# BattleBoard.net
KiCad netlist of a schematic drawn in EasyEDA
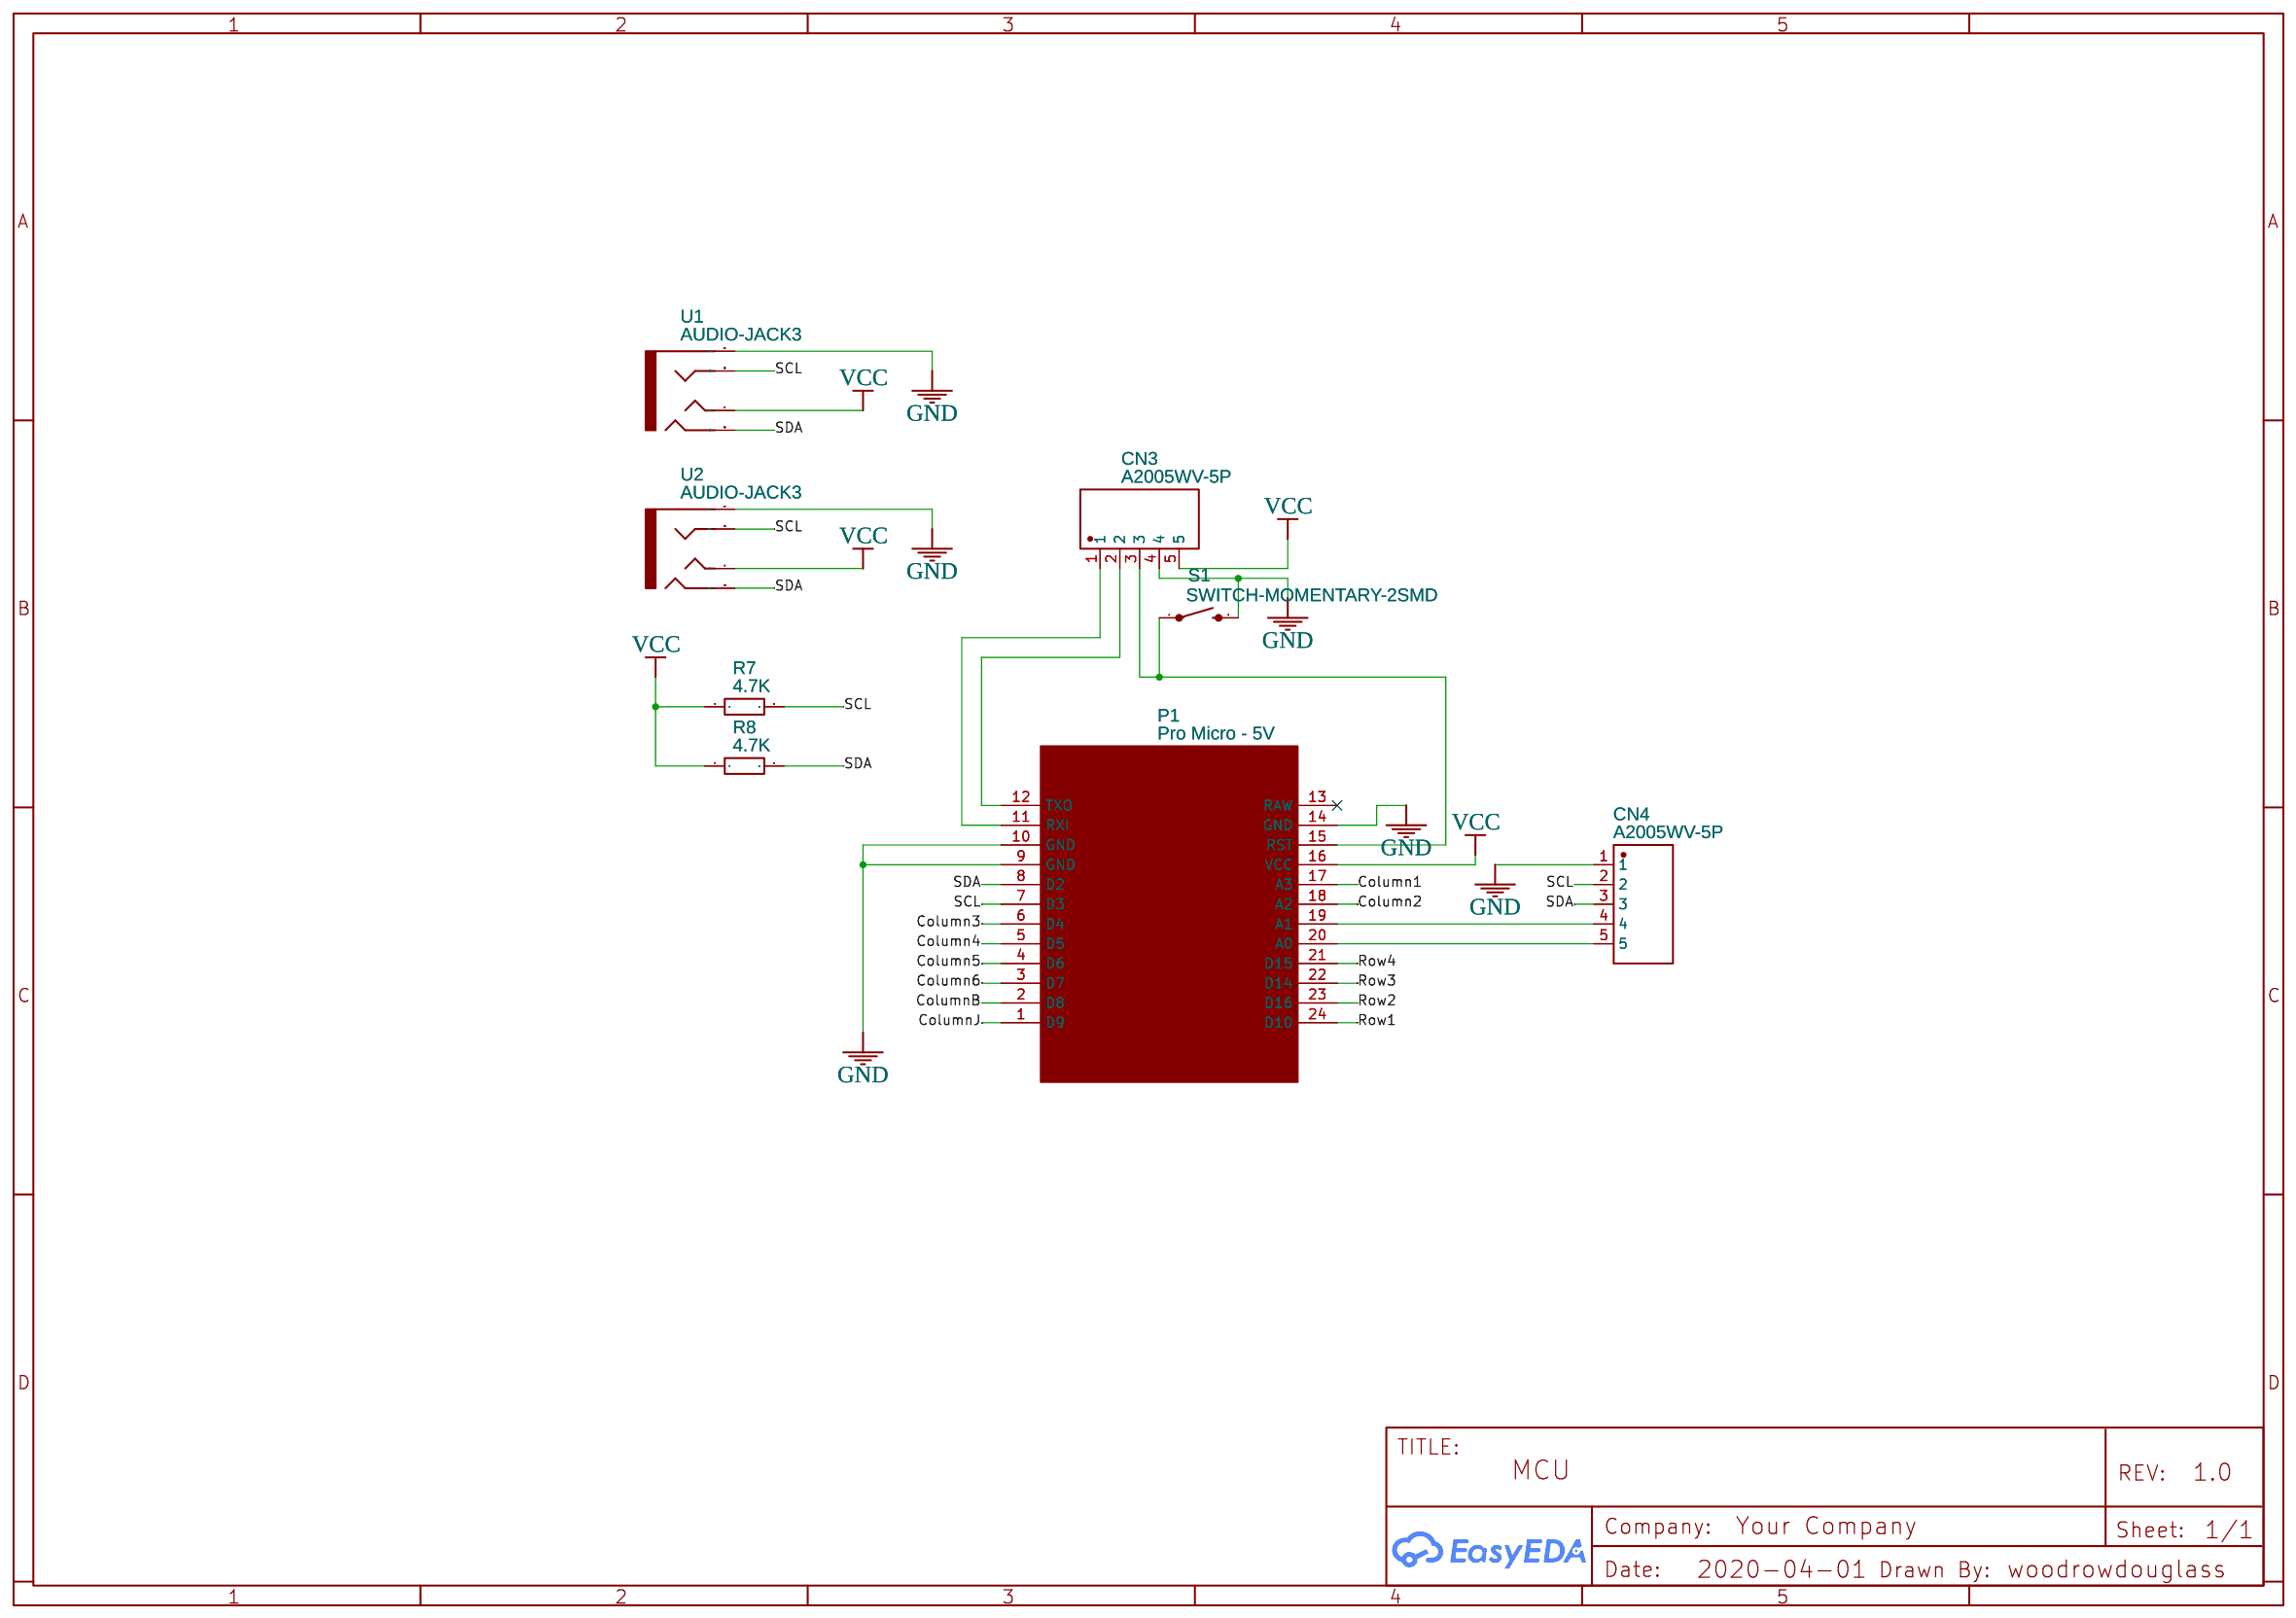
[diagram p0: MCU]
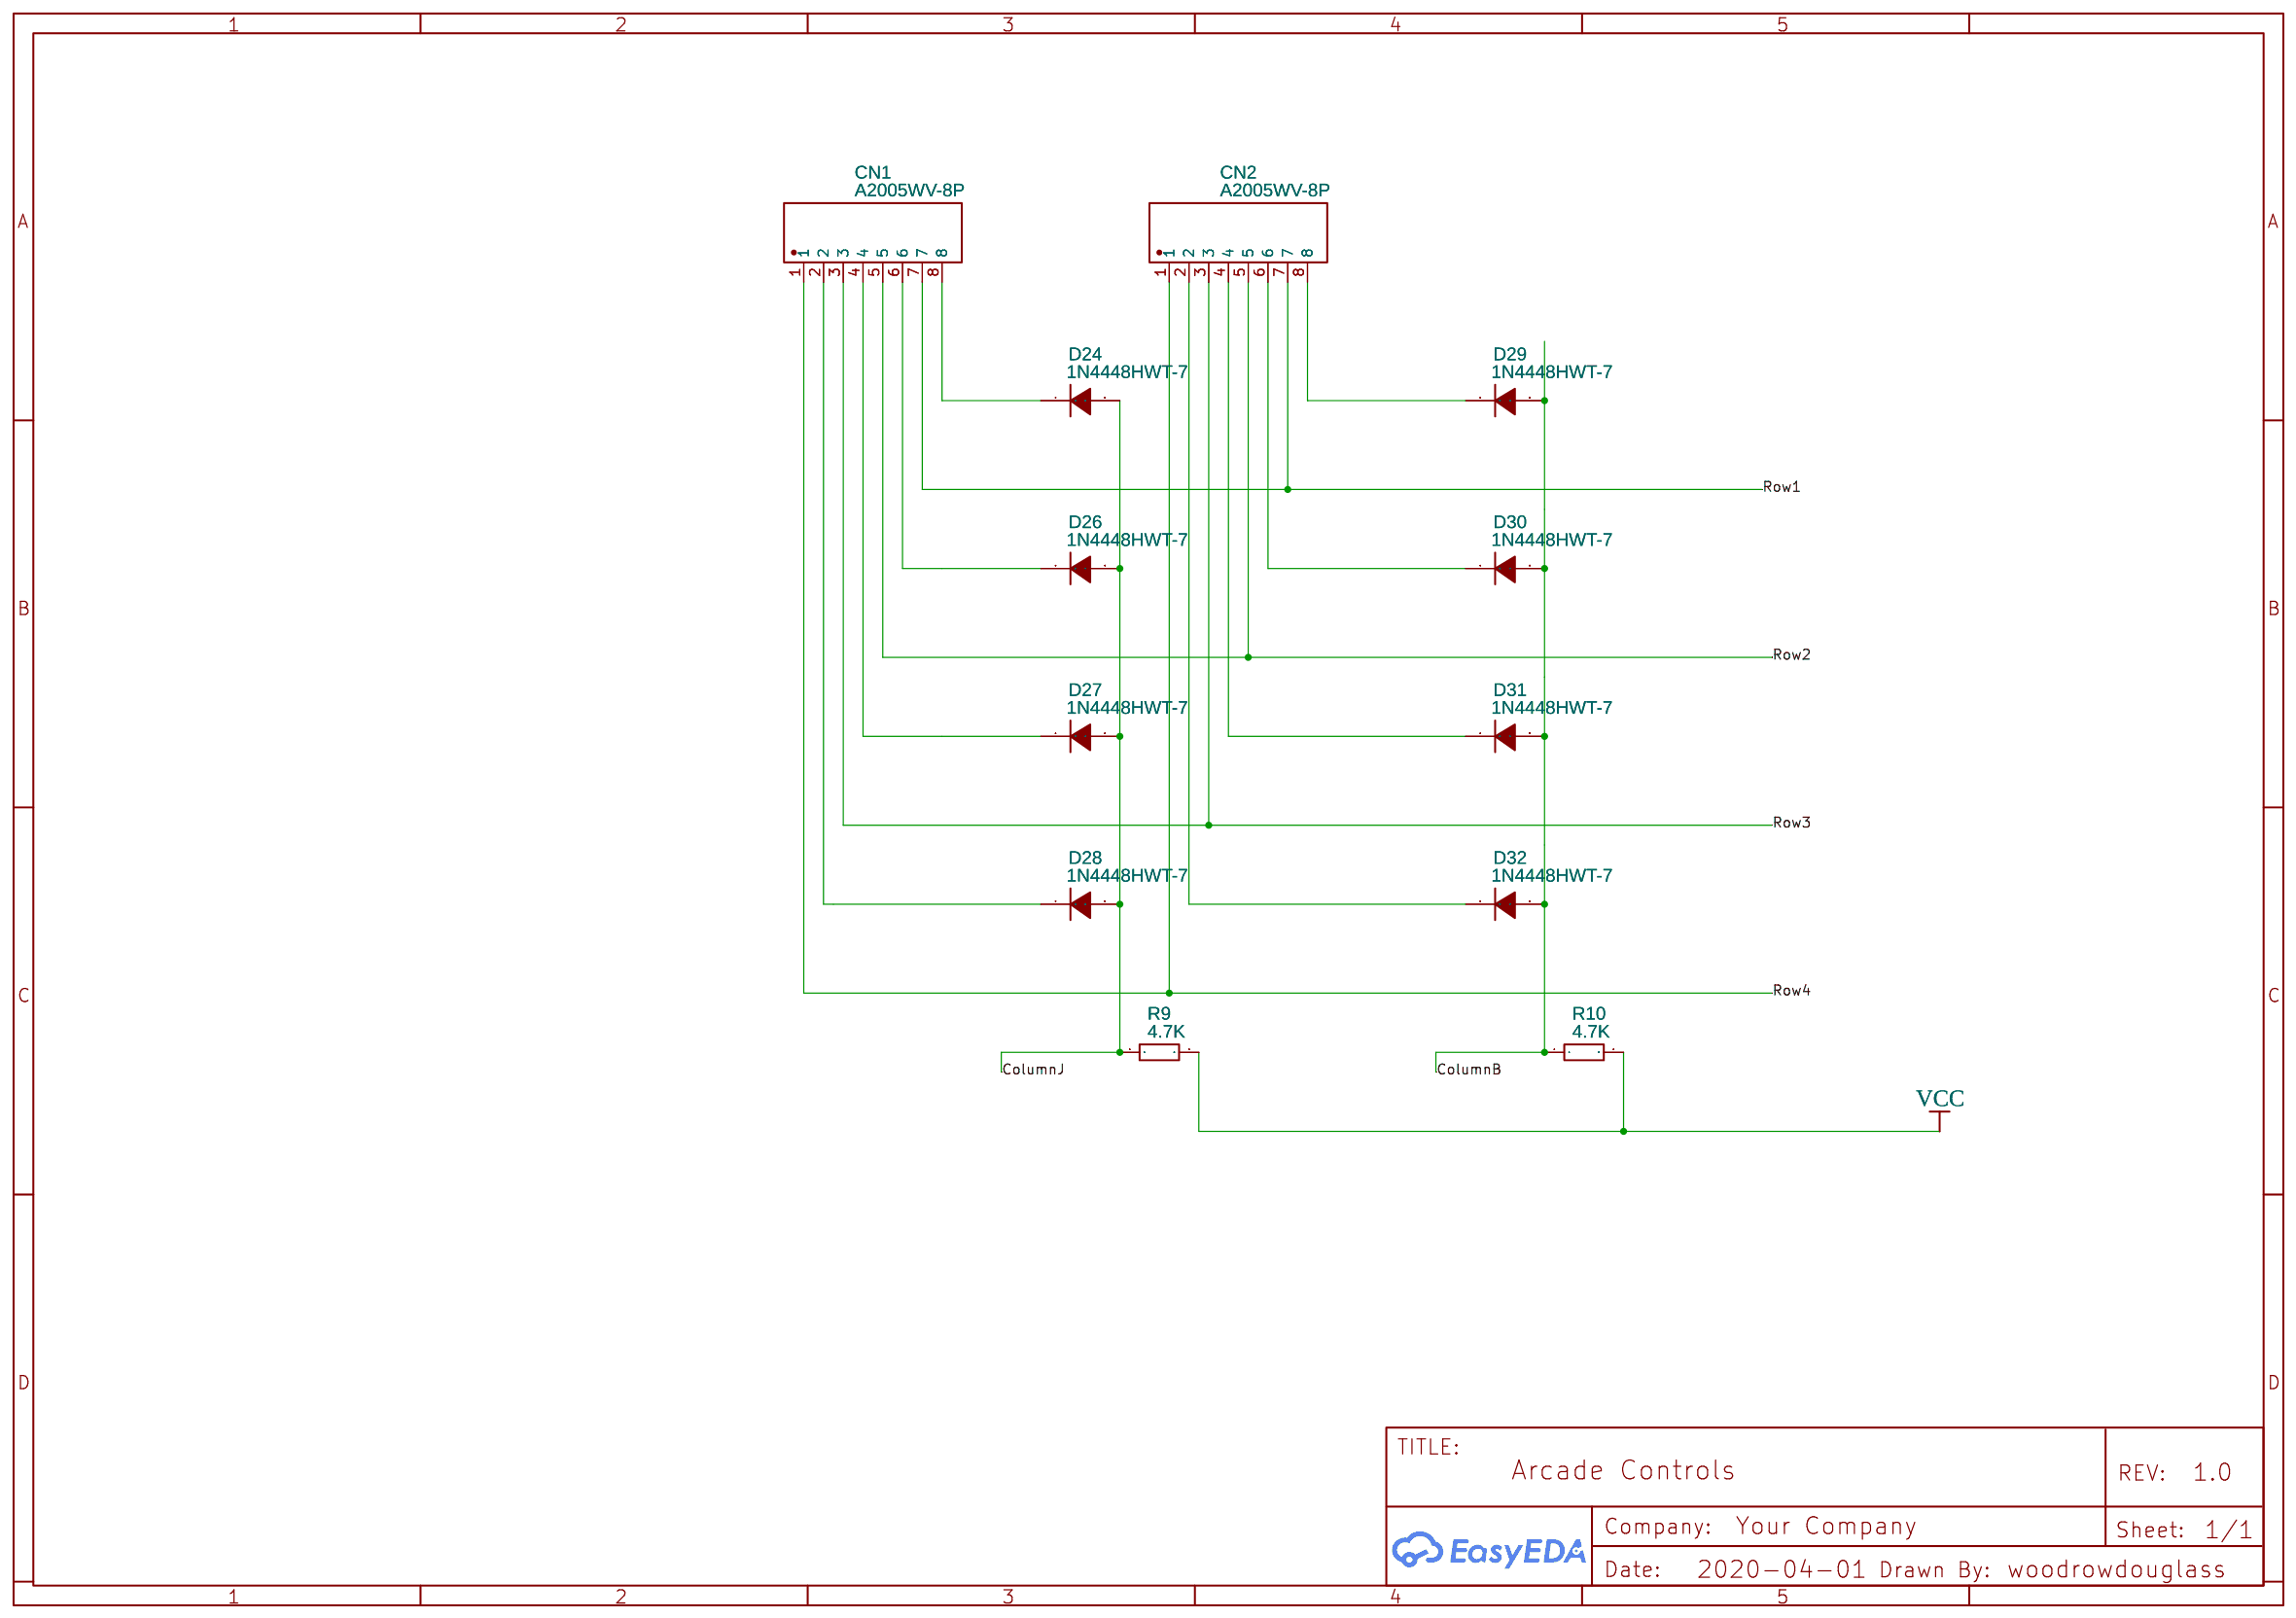
[diagram p1: ArcadeControls]
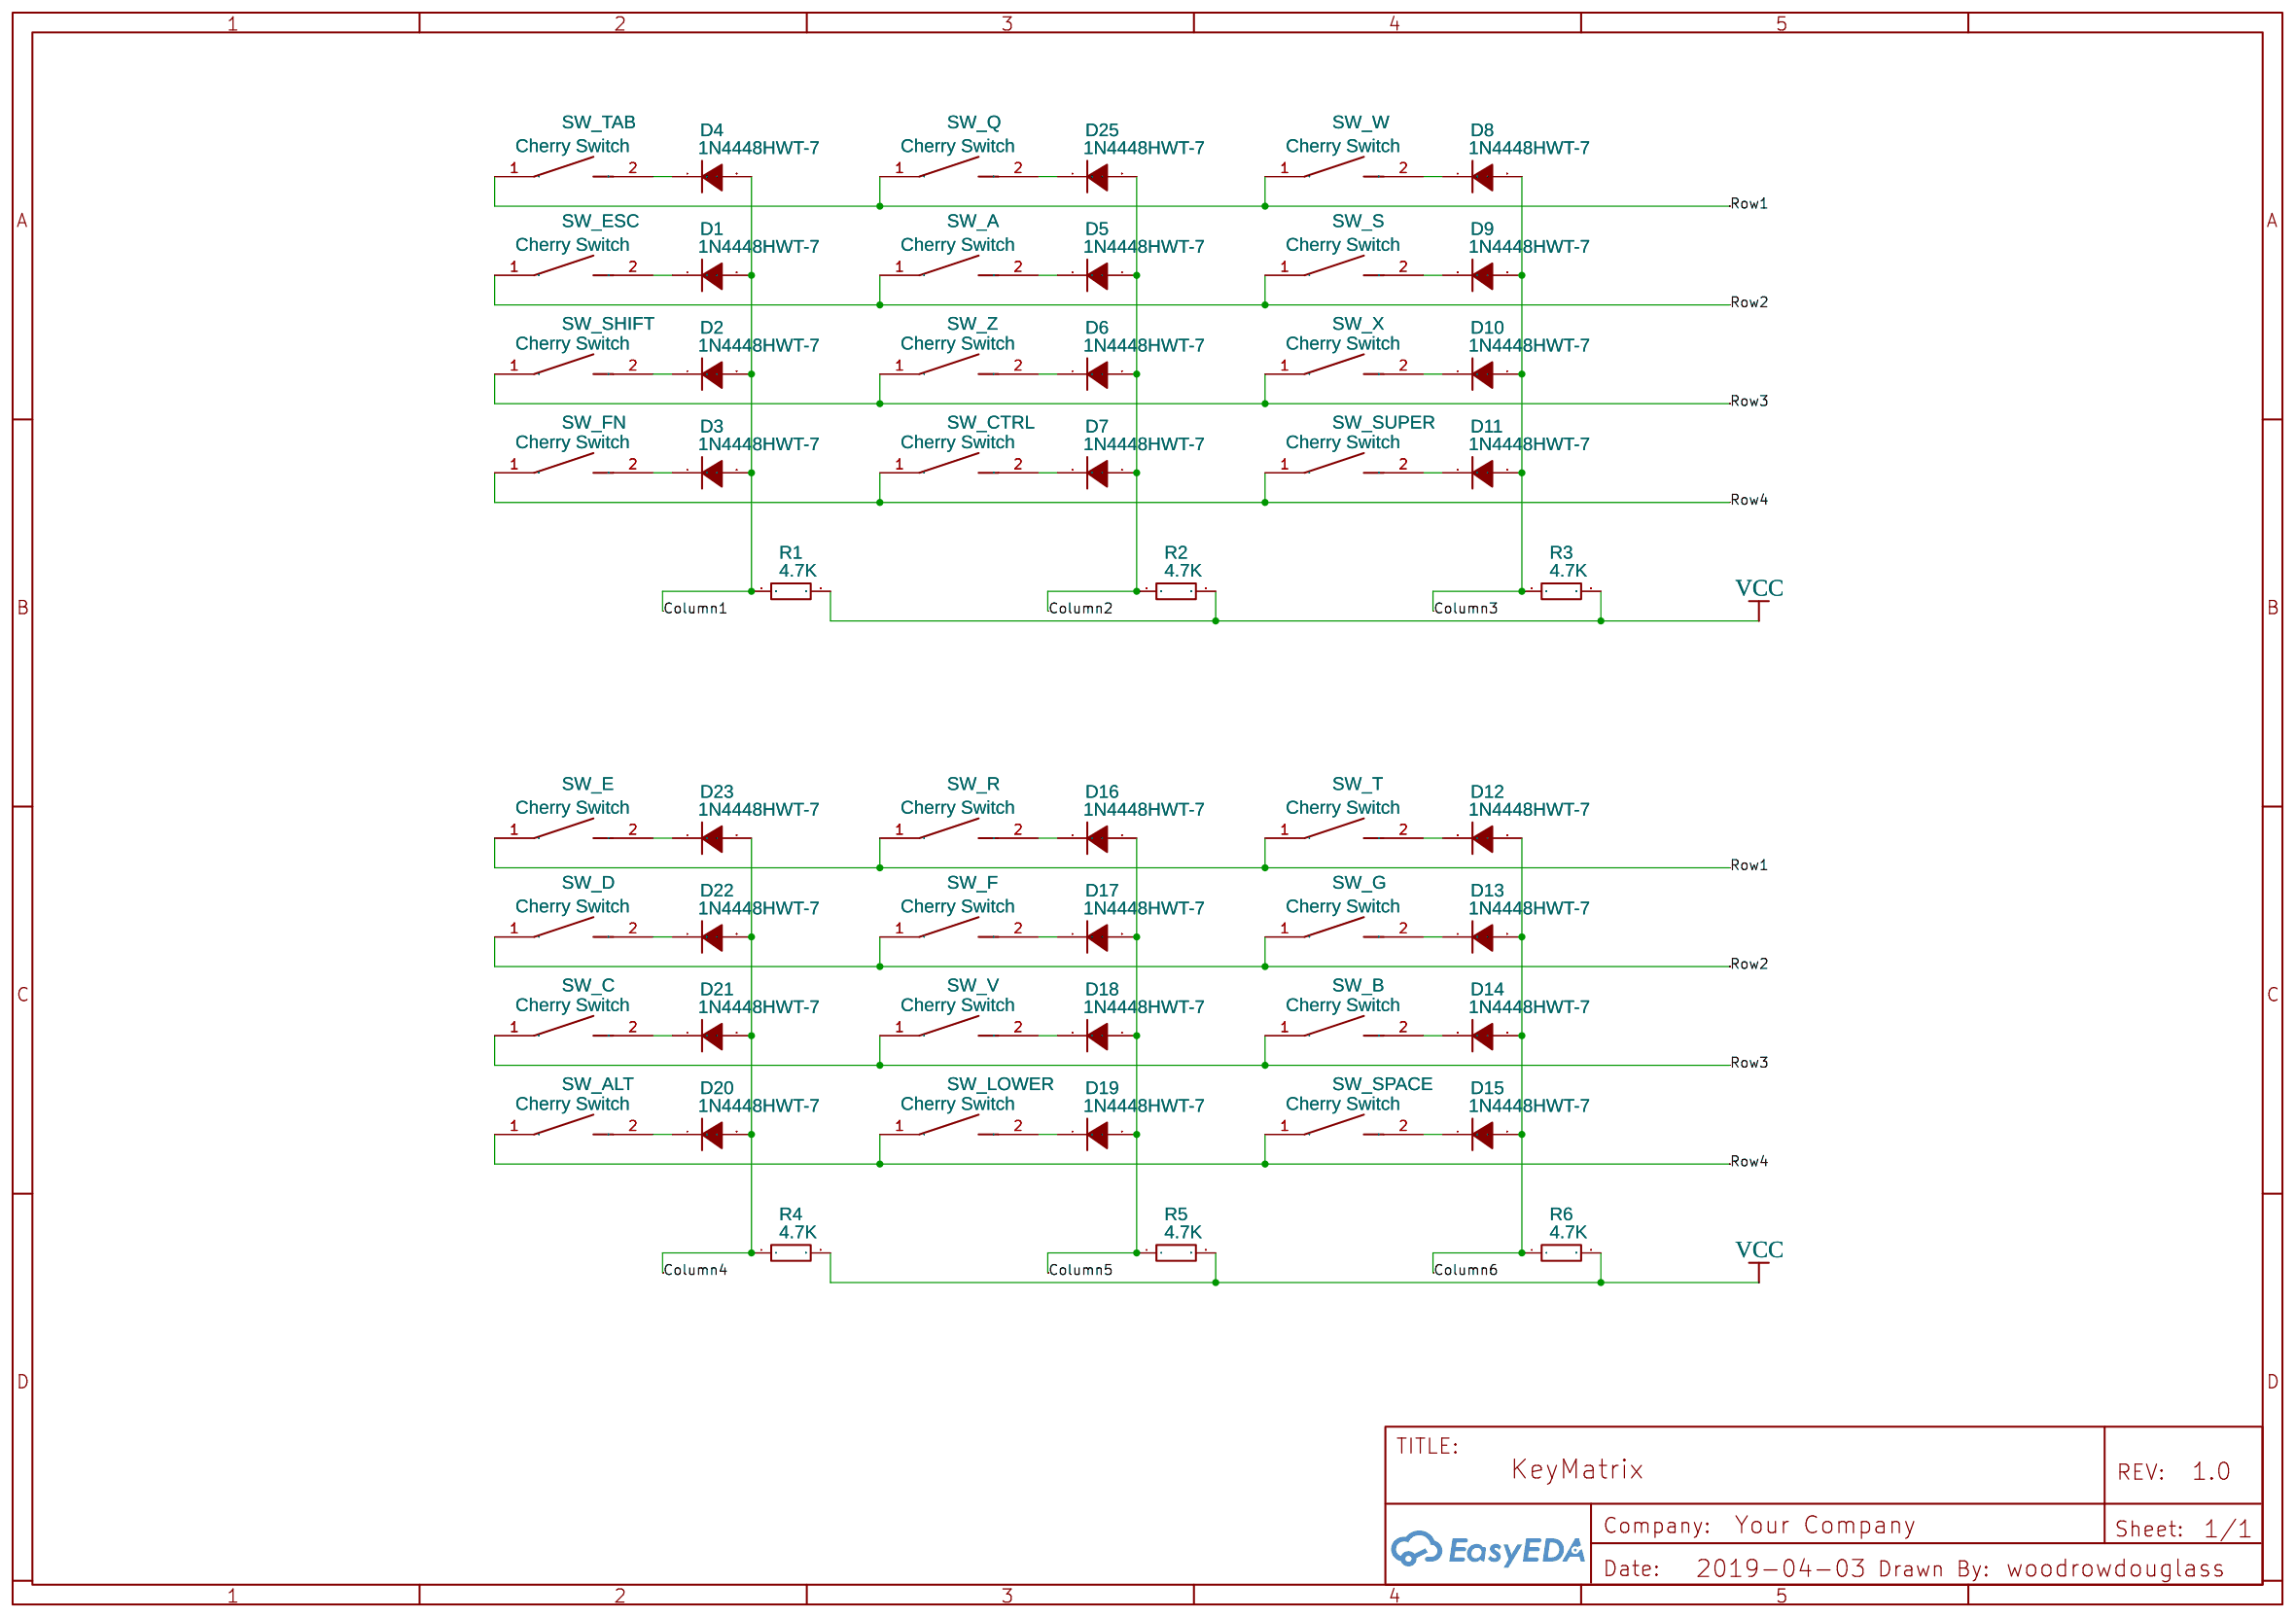
[diagram p2: KeyMatrix]

(export (version "E")
  (design (tool "Eeschema 10.0.6"))
  (components
    (comp (ref "CN3")
      (value "A2005WV-5P")
      (fields (field (name "BOM_Supplier Part") "C225257"))
      (libsource (lib "") (part "A2005WV-5P"))
    )
    (comp (ref "CN4")
      (value "A2005WV-5P")
      (fields (field (name "BOM_Supplier Part") "C225257"))
      (libsource (lib "") (part "A2005WV-5P_1"))
    )
    (comp (ref "P1")
      (value "Pro Micro - 5V")
      (fields (field (name "BOM_Manufacturer Part") "?"))
      (libsource (lib "") (part "Unknown_585_-350"))
    )
    (comp (ref "R7")
      (value "4.7K")
      (fields
        (field (name "BOM_Manufacturer Part") "RMC1/16S-472JTH-M")
        (field (name "BOM_Supplier Part") "C340535")
      )
      (libsource (lib "") (part "RMC1/16S-472JTH-M"))
    )
    (comp (ref "R8")
      (value "4.7K")
      (fields
        (field (name "BOM_Manufacturer Part") "RMC1/16S-472JTH-M")
        (field (name "BOM_Supplier Part") "C340535")
      )
      (libsource (lib "") (part "RMC1/16S-472JTH-M"))
    )
    (comp (ref "S1") (value "SWITCH-MOMENTARY-2SMD") (libsource (lib "") (part "SWITCH-MOMENTARY-2SMD")))
    (comp (ref "U1") (value "AUDIO-JACK3") (libsource (lib "") (part "AUDIO-JACK3")))
    (comp (ref "U2") (value "AUDIO-JACK3") (libsource (lib "") (part "AUDIO-JACK3")))
    (comp (ref "CN1")
      (value "A2005WV-8P")
      (fields (field (name "BOM_Supplier Part") "C225260"))
      (libsource (lib "") (part "A2005WV-8P"))
    )
    (comp (ref "CN2")
      (value "A2005WV-8P")
      (fields (field (name "BOM_Supplier Part") "C225260"))
      (libsource (lib "") (part "A2005WV-8P"))
    )
    (comp (ref "D24")
      (value "1N4448HWT-7")
      (fields (field (name "BOM_Supplier Part") "C139447"))
      (libsource (lib "") (part "1N4448HWT-7"))
    )
    (comp (ref "D26")
      (value "1N4448HWT-7")
      (fields (field (name "BOM_Supplier Part") "C139447"))
      (libsource (lib "") (part "1N4448HWT-7"))
    )
    (comp (ref "D27")
      (value "1N4448HWT-7")
      (fields (field (name "BOM_Supplier Part") "C139447"))
      (libsource (lib "") (part "1N4448HWT-7"))
    )
    (comp (ref "D28")
      (value "1N4448HWT-7")
      (fields (field (name "BOM_Supplier Part") "C139447"))
      (libsource (lib "") (part "1N4448HWT-7"))
    )
    (comp (ref "D29")
      (value "1N4448HWT-7")
      (fields (field (name "BOM_Supplier Part") "C139447"))
      (libsource (lib "") (part "1N4448HWT-7"))
    )
    (comp (ref "D30")
      (value "1N4448HWT-7")
      (fields (field (name "BOM_Supplier Part") "C139447"))
      (libsource (lib "") (part "1N4448HWT-7"))
    )
    (comp (ref "D31")
      (value "1N4448HWT-7")
      (fields (field (name "BOM_Supplier Part") "C139447"))
      (libsource (lib "") (part "1N4448HWT-7"))
    )
    (comp (ref "D32")
      (value "1N4448HWT-7")
      (fields (field (name "BOM_Supplier Part") "C139447"))
      (libsource (lib "") (part "1N4448HWT-7"))
    )
    (comp (ref "R9")
      (value "4.7K")
      (fields
        (field (name "BOM_Manufacturer Part") "RMC1/16S-472JTH-M")
        (field (name "BOM_Supplier Part") "C340535")
      )
      (libsource (lib "") (part "RMC1/16S-472JTH-M"))
    )
    (comp (ref "R10")
      (value "4.7K")
      (fields
        (field (name "BOM_Manufacturer Part") "RMC1/16S-472JTH-M")
        (field (name "BOM_Supplier Part") "C340535")
      )
      (libsource (lib "") (part "RMC1/16S-472JTH-M"))
    )
    (comp (ref "D1")
      (value "1N4448HWT-7")
      (fields (field (name "BOM_Supplier Part") "C139447"))
      (libsource (lib "") (part "1N4448HWT-7"))
    )
    (comp (ref "D2")
      (value "1N4448HWT-7")
      (fields (field (name "BOM_Supplier Part") "C139447"))
      (libsource (lib "") (part "1N4448HWT-7"))
    )
    (comp (ref "D3")
      (value "1N4448HWT-7")
      (fields (field (name "BOM_Supplier Part") "C139447"))
      (libsource (lib "") (part "1N4448HWT-7"))
    )
    (comp (ref "D4")
      (value "1N4448HWT-7")
      (fields (field (name "BOM_Supplier Part") "C139447"))
      (libsource (lib "") (part "1N4448HWT-7"))
    )
    (comp (ref "D5")
      (value "1N4448HWT-7")
      (fields (field (name "BOM_Supplier Part") "C139447"))
      (libsource (lib "") (part "1N4448HWT-7"))
    )
    (comp (ref "D6")
      (value "1N4448HWT-7")
      (fields (field (name "BOM_Supplier Part") "C139447"))
      (libsource (lib "") (part "1N4448HWT-7"))
    )
    (comp (ref "D7")
      (value "1N4448HWT-7")
      (fields (field (name "BOM_Supplier Part") "C139447"))
      (libsource (lib "") (part "1N4448HWT-7"))
    )
    (comp (ref "D8")
      (value "1N4448HWT-7")
      (fields (field (name "BOM_Supplier Part") "C139447"))
      (libsource (lib "") (part "1N4448HWT-7"))
    )
    (comp (ref "D9")
      (value "1N4448HWT-7")
      (fields (field (name "BOM_Supplier Part") "C139447"))
      (libsource (lib "") (part "1N4448HWT-7"))
    )
    (comp (ref "D10")
      (value "1N4448HWT-7")
      (fields (field (name "BOM_Supplier Part") "C139447"))
      (libsource (lib "") (part "1N4448HWT-7"))
    )
    (comp (ref "D11")
      (value "1N4448HWT-7")
      (fields (field (name "BOM_Supplier Part") "C139447"))
      (libsource (lib "") (part "1N4448HWT-7"))
    )
    (comp (ref "D12")
      (value "1N4448HWT-7")
      (fields (field (name "BOM_Supplier Part") "C139447"))
      (libsource (lib "") (part "1N4448HWT-7"))
    )
    (comp (ref "D13")
      (value "1N4448HWT-7")
      (fields (field (name "BOM_Supplier Part") "C139447"))
      (libsource (lib "") (part "1N4448HWT-7"))
    )
    (comp (ref "D14")
      (value "1N4448HWT-7")
      (fields (field (name "BOM_Supplier Part") "C139447"))
      (libsource (lib "") (part "1N4448HWT-7"))
    )
    (comp (ref "D15")
      (value "1N4448HWT-7")
      (fields (field (name "BOM_Supplier Part") "C139447"))
      (libsource (lib "") (part "1N4448HWT-7"))
    )
    (comp (ref "D16")
      (value "1N4448HWT-7")
      (fields (field (name "BOM_Supplier Part") "C139447"))
      (libsource (lib "") (part "1N4448HWT-7"))
    )
    (comp (ref "D17")
      (value "1N4448HWT-7")
      (fields (field (name "BOM_Supplier Part") "C139447"))
      (libsource (lib "") (part "1N4448HWT-7"))
    )
    (comp (ref "D18")
      (value "1N4448HWT-7")
      (fields (field (name "BOM_Supplier Part") "C139447"))
      (libsource (lib "") (part "1N4448HWT-7"))
    )
    (comp (ref "D19")
      (value "1N4448HWT-7")
      (fields (field (name "BOM_Supplier Part") "C139447"))
      (libsource (lib "") (part "1N4448HWT-7"))
    )
    (comp (ref "D20")
      (value "1N4448HWT-7")
      (fields (field (name "BOM_Supplier Part") "C139447"))
      (libsource (lib "") (part "1N4448HWT-7"))
    )
    (comp (ref "D21")
      (value "1N4448HWT-7")
      (fields (field (name "BOM_Supplier Part") "C139447"))
      (libsource (lib "") (part "1N4448HWT-7"))
    )
    (comp (ref "D22")
      (value "1N4448HWT-7")
      (fields (field (name "BOM_Supplier Part") "C139447"))
      (libsource (lib "") (part "1N4448HWT-7"))
    )
    (comp (ref "D23")
      (value "1N4448HWT-7")
      (fields (field (name "BOM_Supplier Part") "C139447"))
      (libsource (lib "") (part "1N4448HWT-7"))
    )
    (comp (ref "D25")
      (value "1N4448HWT-7")
      (fields (field (name "BOM_Supplier Part") "C139447"))
      (libsource (lib "") (part "1N4448HWT-7"))
    )
    (comp (ref "R1")
      (value "4.7K")
      (fields
        (field (name "BOM_Manufacturer Part") "RMC1/16S-472JTH-M")
        (field (name "BOM_Supplier Part") "C340535")
      )
      (libsource (lib "") (part "RMC1/16S-472JTH-M"))
    )
    (comp (ref "R2")
      (value "4.7K")
      (fields
        (field (name "BOM_Manufacturer Part") "RMC1/16S-472JTH-M")
        (field (name "BOM_Supplier Part") "C340535")
      )
      (libsource (lib "") (part "RMC1/16S-472JTH-M"))
    )
    (comp (ref "R3")
      (value "4.7K")
      (fields
        (field (name "BOM_Manufacturer Part") "RMC1/16S-472JTH-M")
        (field (name "BOM_Supplier Part") "C340535")
      )
      (libsource (lib "") (part "RMC1/16S-472JTH-M"))
    )
    (comp (ref "R4")
      (value "4.7K")
      (fields
        (field (name "BOM_Manufacturer Part") "RMC1/16S-472JTH-M")
        (field (name "BOM_Supplier Part") "C340535")
      )
      (libsource (lib "") (part "RMC1/16S-472JTH-M"))
    )
    (comp (ref "R5")
      (value "4.7K")
      (fields
        (field (name "BOM_Manufacturer Part") "RMC1/16S-472JTH-M")
        (field (name "BOM_Supplier Part") "C340535")
      )
      (libsource (lib "") (part "RMC1/16S-472JTH-M"))
    )
    (comp (ref "R6")
      (value "4.7K")
      (fields
        (field (name "BOM_Manufacturer Part") "RMC1/16S-472JTH-M")
        (field (name "BOM_Supplier Part") "C340535")
      )
      (libsource (lib "") (part "RMC1/16S-472JTH-M"))
    )
    (comp (ref "SW_A")
      (value "Cherry Switch")
      (fields (field (name "BOM_Manufacturer Part") "CHERRY"))
      (libsource (lib "") (part "CHERRY_MX_LABELED_16"))
    )
    (comp (ref "SW_ALT")
      (value "Cherry Switch")
      (fields (field (name "BOM_Manufacturer Part") "CHERRY"))
      (libsource (lib "") (part "CHERRY_MX_LABELED_1"))
    )
    (comp (ref "SW_B")
      (value "Cherry Switch")
      (fields (field (name "BOM_Manufacturer Part") "CHERRY"))
      (libsource (lib "") (part "CHERRY_MX_LABELED_15"))
    )
    (comp (ref "SW_C")
      (value "Cherry Switch")
      (fields (field (name "BOM_Manufacturer Part") "CHERRY"))
      (libsource (lib "") (part "CHERRY_MX_LABELED_5"))
    )
    (comp (ref "SW_CTRL")
      (value "Cherry Switch")
      (fields (field (name "BOM_Manufacturer Part") "CHERRY"))
      (libsource (lib "") (part "CHERRY_MX_LABELED_9"))
    )
    (comp (ref "SW_D")
      (value "Cherry Switch")
      (fields (field (name "BOM_Manufacturer Part") "CHERRY"))
      (libsource (lib "") (part "CHERRY_MX_LABELED_3"))
    )
    (comp (ref "SW_E")
      (value "Cherry Switch")
      (fields (field (name "BOM_Manufacturer Part") "CHERRY"))
      (libsource (lib "") (part "CHERRY_MX_LABELED_2"))
    )
    (comp (ref "SW_ESC")
      (value "Cherry Switch")
      (fields (field (name "BOM_Manufacturer Part") "CHERRY"))
      (libsource (lib "") (part "CHERRY_MX_LABELED_18"))
    )
    (comp (ref "SW_F")
      (value "Cherry Switch")
      (fields (field (name "BOM_Manufacturer Part") "CHERRY"))
      (libsource (lib "") (part "CHERRY_MX_LABELED_4"))
    )
    (comp (ref "SW_FN")
      (value "Cherry Switch")
      (fields (field (name "BOM_Manufacturer Part") "CHERRY"))
      (libsource (lib "") (part "CHERRY_MX_LABELED_10"))
    )
    (comp (ref "SW_G")
      (value "Cherry Switch")
      (fields (field (name "BOM_Manufacturer Part") "CHERRY"))
      (libsource (lib "") (part "CHERRY_MX_LABELED_12"))
    )
    (comp (ref "SW_LOWER")
      (value "Cherry Switch")
      (fields (field (name "BOM_Manufacturer Part") "CHERRY"))
      (libsource (lib "") (part "CHERRY_MX_LABELED_13"))
    )
    (comp (ref "SW_Q")
      (value "Cherry Switch")
      (fields (field (name "BOM_Manufacturer Part") "CHERRY"))
      (libsource (lib "") (part "CHERRY_MX_LABELED_22"))
    )
    (comp (ref "SW_R")
      (value "Cherry Switch")
      (fields (field (name "BOM_Manufacturer Part") "CHERRY"))
      (libsource (lib "") (part "CHERRY_MX_LABELED_11"))
    )
    (comp (ref "SW_S")
      (value "Cherry Switch")
      (fields (field (name "BOM_Manufacturer Part") "CHERRY"))
      (libsource (lib "") (part "CHERRY_MX_LABELED_23"))
    )
    (comp (ref "SW_SHIFT")
      (value "Cherry Switch")
      (fields (field (name "BOM_Manufacturer Part") "CHERRY"))
      (libsource (lib "") (part "CHERRY_MX_LABELED_6"))
    )
    (comp (ref "SW_SPACE")
      (value "Cherry Switch")
      (fields (field (name "BOM_Manufacturer Part") "CHERRY"))
      (libsource (lib "") (part "CHERRY_MX_LABELED_7"))
    )
    (comp (ref "SW_SUPER")
      (value "Cherry Switch")
      (fields (field (name "BOM_Manufacturer Part") "CHERRY"))
      (libsource (lib "") (part "CHERRY_MX_LABELED_14"))
    )
    (comp (ref "SW_T")
      (value "Cherry Switch")
      (fields (field (name "BOM_Manufacturer Part") "CHERRY"))
      (libsource (lib "") (part "CHERRY_MX_LABELED_17"))
    )
    (comp (ref "SW_TAB")
      (value "Cherry Switch")
      (fields (field (name "BOM_Manufacturer Part") "CHERRY"))
      (libsource (lib "") (part "CHERRY_MX_LABELED_8"))
    )
    (comp (ref "SW_V")
      (value "Cherry Switch")
      (fields (field (name "BOM_Manufacturer Part") "CHERRY"))
      (libsource (lib "") (part "CHERRY_MX_LABELED"))
    )
    (comp (ref "SW_W")
      (value "Cherry Switch")
      (fields (field (name "BOM_Manufacturer Part") "CHERRY"))
      (libsource (lib "") (part "CHERRY_MX_LABELED_21"))
    )
    (comp (ref "SW_X")
      (value "Cherry Switch")
      (fields (field (name "BOM_Manufacturer Part") "CHERRY"))
      (libsource (lib "") (part "CHERRY_MX_LABELED_19"))
    )
    (comp (ref "SW_Z")
      (value "Cherry Switch")
      (fields (field (name "BOM_Manufacturer Part") "CHERRY"))
      (libsource (lib "") (part "CHERRY_MX_LABELED_20"))
    )
  )
  (nets
    (net (code "1") (name "Column1") (class "Default")
      (node (ref "D1") (pin "2") (pinfunction "A_2") (pintype "unspecified"))
      (node (ref "D2") (pin "2") (pinfunction "A_2") (pintype "unspecified"))
      (node (ref "D3") (pin "2") (pinfunction "A_2") (pintype "unspecified"))
      (node (ref "D4") (pin "2") (pinfunction "A_2") (pintype "unspecified"))
      (node (ref "P1") (pin "17") (pinfunction "A3_17") (pintype "unspecified"))
      (node (ref "R1") (pin "1") (pinfunction "1_1") (pintype "unspecified"))
    )
    (net (code "2") (name "Column2") (class "Default")
      (node (ref "D25") (pin "2") (pinfunction "A_2") (pintype "unspecified"))
      (node (ref "D5") (pin "2") (pinfunction "A_2") (pintype "unspecified"))
      (node (ref "D6") (pin "2") (pinfunction "A_2") (pintype "unspecified"))
      (node (ref "D7") (pin "2") (pinfunction "A_2") (pintype "unspecified"))
      (node (ref "P1") (pin "18") (pinfunction "A2_18") (pintype "unspecified"))
      (node (ref "R2") (pin "1") (pinfunction "1_1") (pintype "unspecified"))
    )
    (net (code "3") (name "Column3") (class "Default")
      (node (ref "D10") (pin "2") (pinfunction "A_2") (pintype "unspecified"))
      (node (ref "D11") (pin "2") (pinfunction "A_2") (pintype "unspecified"))
      (node (ref "D8") (pin "2") (pinfunction "A_2") (pintype "unspecified"))
      (node (ref "D9") (pin "2") (pinfunction "A_2") (pintype "unspecified"))
      (node (ref "P1") (pin "6") (pinfunction "D4_6") (pintype "unspecified"))
      (node (ref "R3") (pin "1") (pinfunction "1_1") (pintype "unspecified"))
    )
    (net (code "4") (name "Column4") (class "Default")
      (node (ref "D20") (pin "2") (pinfunction "A_2") (pintype "unspecified"))
      (node (ref "D21") (pin "2") (pinfunction "A_2") (pintype "unspecified"))
      (node (ref "D22") (pin "2") (pinfunction "A_2") (pintype "unspecified"))
      (node (ref "D23") (pin "2") (pinfunction "A_2") (pintype "unspecified"))
      (node (ref "P1") (pin "5") (pinfunction "D5_5") (pintype "unspecified"))
      (node (ref "R4") (pin "1") (pinfunction "1_1") (pintype "unspecified"))
    )
    (net (code "5") (name "Column5") (class "Default")
      (node (ref "D16") (pin "2") (pinfunction "A_2") (pintype "unspecified"))
      (node (ref "D17") (pin "2") (pinfunction "A_2") (pintype "unspecified"))
      (node (ref "D18") (pin "2") (pinfunction "A_2") (pintype "unspecified"))
      (node (ref "D19") (pin "2") (pinfunction "A_2") (pintype "unspecified"))
      (node (ref "P1") (pin "4") (pinfunction "D6_4") (pintype "unspecified"))
      (node (ref "R5") (pin "1") (pinfunction "1_1") (pintype "unspecified"))
    )
    (net (code "6") (name "Column6") (class "Default")
      (node (ref "D12") (pin "2") (pinfunction "A_2") (pintype "unspecified"))
      (node (ref "D13") (pin "2") (pinfunction "A_2") (pintype "unspecified"))
      (node (ref "D14") (pin "2") (pinfunction "A_2") (pintype "unspecified"))
      (node (ref "D15") (pin "2") (pinfunction "A_2") (pintype "unspecified"))
      (node (ref "P1") (pin "3") (pinfunction "D7_3") (pintype "unspecified"))
      (node (ref "R6") (pin "1") (pinfunction "1_1") (pintype "unspecified"))
    )
    (net (code "7") (name "ColumnB") (class "Default")
      (node (ref "D29") (pin "2") (pinfunction "A_2") (pintype "unspecified"))
      (node (ref "D30") (pin "2") (pinfunction "A_2") (pintype "unspecified"))
      (node (ref "D31") (pin "2") (pinfunction "A_2") (pintype "unspecified"))
      (node (ref "D32") (pin "2") (pinfunction "A_2") (pintype "unspecified"))
      (node (ref "P1") (pin "2") (pinfunction "D8_2") (pintype "unspecified"))
      (node (ref "R10") (pin "1") (pinfunction "1_1") (pintype "unspecified"))
    )
    (net (code "8") (name "ColumnJ") (class "Default")
      (node (ref "D24") (pin "2") (pinfunction "A_2") (pintype "unspecified"))
      (node (ref "D26") (pin "2") (pinfunction "A_2") (pintype "unspecified"))
      (node (ref "D27") (pin "2") (pinfunction "A_2") (pintype "unspecified"))
      (node (ref "D28") (pin "2") (pinfunction "A_2") (pintype "unspecified"))
      (node (ref "P1") (pin "1") (pinfunction "D9_1") (pintype "unspecified"))
      (node (ref "R9") (pin "1") (pinfunction "1_1") (pintype "unspecified"))
    )
    (net (code "9") (name "GND") (class "Default")
      (node (ref "CN3") (pin "4") (pinfunction "4_4") (pintype "unspecified"))
      (node (ref "CN4") (pin "1") (pinfunction "1_1") (pintype "unspecified"))
      (node (ref "P1") (pin "10") (pinfunction "GND_10") (pintype "unspecified"))
      (node (ref "P1") (pin "14") (pinfunction "GND_14") (pintype "unspecified"))
      (node (ref "P1") (pin "9") (pinfunction "GND_9") (pintype "unspecified"))
      (node (ref "S1") (pin "3") (pinfunction "2_3") (pintype "unspecified"))
      (node (ref "U1") (pin "EARTH") (pinfunction "EARTH_EARTH") (pintype "unspecified"))
      (node (ref "U2") (pin "EARTH") (pinfunction "EARTH_EARTH") (pintype "unspecified"))
    )
    (net (code "10") (name "Net-(D1-C)") (class "Default")
      (node (ref "D1") (pin "1") (pinfunction "C_1") (pintype "unspecified"))
      (node (ref "SW_ESC") (pin "2") (pinfunction "2_2") (pintype "unspecified"))
    )
    (net (code "11") (name "Net-(D2-C)") (class "Default")
      (node (ref "D2") (pin "1") (pinfunction "C_1") (pintype "unspecified"))
      (node (ref "SW_SHIFT") (pin "2") (pinfunction "2_2") (pintype "unspecified"))
    )
    (net (code "12") (name "Net-(D3-C)") (class "Default")
      (node (ref "D3") (pin "1") (pinfunction "C_1") (pintype "unspecified"))
      (node (ref "SW_FN") (pin "2") (pinfunction "2_2") (pintype "unspecified"))
    )
    (net (code "13") (name "Net-(D4-C)") (class "Default")
      (node (ref "D4") (pin "1") (pinfunction "C_1") (pintype "unspecified"))
      (node (ref "SW_TAB") (pin "2") (pinfunction "2_2") (pintype "unspecified"))
    )
    (net (code "14") (name "Net-(D5-C)") (class "Default")
      (node (ref "D5") (pin "1") (pinfunction "C_1") (pintype "unspecified"))
      (node (ref "SW_A") (pin "2") (pinfunction "2_2") (pintype "unspecified"))
    )
    (net (code "15") (name "Net-(D6-C)") (class "Default")
      (node (ref "D6") (pin "1") (pinfunction "C_1") (pintype "unspecified"))
      (node (ref "SW_Z") (pin "2") (pinfunction "2_2") (pintype "unspecified"))
    )
    (net (code "16") (name "Net-(D7-C)") (class "Default")
      (node (ref "D7") (pin "1") (pinfunction "C_1") (pintype "unspecified"))
      (node (ref "SW_CTRL") (pin "2") (pinfunction "2_2") (pintype "unspecified"))
    )
    (net (code "17") (name "Net-(D8-C)") (class "Default")
      (node (ref "D8") (pin "1") (pinfunction "C_1") (pintype "unspecified"))
      (node (ref "SW_W") (pin "2") (pinfunction "2_2") (pintype "unspecified"))
    )
    (net (code "18") (name "Net-(D9-C)") (class "Default")
      (node (ref "D9") (pin "1") (pinfunction "C_1") (pintype "unspecified"))
      (node (ref "SW_S") (pin "2") (pinfunction "2_2") (pintype "unspecified"))
    )
    (net (code "19") (name "Net-(D10-C)") (class "Default")
      (node (ref "D10") (pin "1") (pinfunction "C_1") (pintype "unspecified"))
      (node (ref "SW_X") (pin "2") (pinfunction "2_2") (pintype "unspecified"))
    )
    (net (code "20") (name "Net-(D11-C)") (class "Default")
      (node (ref "D11") (pin "1") (pinfunction "C_1") (pintype "unspecified"))
      (node (ref "SW_SUPER") (pin "2") (pinfunction "2_2") (pintype "unspecified"))
    )
    (net (code "21") (name "Net-(D12-C)") (class "Default")
      (node (ref "D12") (pin "1") (pinfunction "C_1") (pintype "unspecified"))
      (node (ref "SW_T") (pin "2") (pinfunction "2_2") (pintype "unspecified"))
    )
    (net (code "22") (name "Net-(D13-C)") (class "Default")
      (node (ref "D13") (pin "1") (pinfunction "C_1") (pintype "unspecified"))
      (node (ref "SW_G") (pin "2") (pinfunction "2_2") (pintype "unspecified"))
    )
    (net (code "23") (name "Net-(D14-C)") (class "Default")
      (node (ref "D14") (pin "1") (pinfunction "C_1") (pintype "unspecified"))
      (node (ref "SW_B") (pin "2") (pinfunction "2_2") (pintype "unspecified"))
    )
    (net (code "24") (name "Net-(D15-C)") (class "Default")
      (node (ref "D15") (pin "1") (pinfunction "C_1") (pintype "unspecified"))
      (node (ref "SW_SPACE") (pin "2") (pinfunction "2_2") (pintype "unspecified"))
    )
    (net (code "25") (name "Net-(D16-C)") (class "Default")
      (node (ref "D16") (pin "1") (pinfunction "C_1") (pintype "unspecified"))
      (node (ref "SW_R") (pin "2") (pinfunction "2_2") (pintype "unspecified"))
    )
    (net (code "26") (name "Net-(D17-C)") (class "Default")
      (node (ref "D17") (pin "1") (pinfunction "C_1") (pintype "unspecified"))
      (node (ref "SW_F") (pin "2") (pinfunction "2_2") (pintype "unspecified"))
    )
    (net (code "27") (name "Net-(D18-C)") (class "Default")
      (node (ref "D18") (pin "1") (pinfunction "C_1") (pintype "unspecified"))
      (node (ref "SW_V") (pin "2") (pinfunction "2_2") (pintype "unspecified"))
    )
    (net (code "28") (name "Net-(D19-C)") (class "Default")
      (node (ref "D19") (pin "1") (pinfunction "C_1") (pintype "unspecified"))
      (node (ref "SW_LOWER") (pin "2") (pinfunction "2_2") (pintype "unspecified"))
    )
    (net (code "29") (name "Net-(D20-C)") (class "Default")
      (node (ref "D20") (pin "1") (pinfunction "C_1") (pintype "unspecified"))
      (node (ref "SW_ALT") (pin "2") (pinfunction "2_2") (pintype "unspecified"))
    )
    (net (code "30") (name "Net-(D21-C)") (class "Default")
      (node (ref "D21") (pin "1") (pinfunction "C_1") (pintype "unspecified"))
      (node (ref "SW_C") (pin "2") (pinfunction "2_2") (pintype "unspecified"))
    )
    (net (code "31") (name "Net-(D22-C)") (class "Default")
      (node (ref "D22") (pin "1") (pinfunction "C_1") (pintype "unspecified"))
      (node (ref "SW_D") (pin "2") (pinfunction "2_2") (pintype "unspecified"))
    )
    (net (code "32") (name "Net-(D23-C)") (class "Default")
      (node (ref "D23") (pin "1") (pinfunction "C_1") (pintype "unspecified"))
      (node (ref "SW_E") (pin "2") (pinfunction "2_2") (pintype "unspecified"))
    )
    (net (code "33") (name "Net-(D24-C)") (class "Default")
      (node (ref "CN1") (pin "8") (pinfunction "8_8") (pintype "unspecified"))
      (node (ref "D24") (pin "1") (pinfunction "C_1") (pintype "unspecified"))
    )
    (net (code "34") (name "Net-(D25-C)") (class "Default")
      (node (ref "D25") (pin "1") (pinfunction "C_1") (pintype "unspecified"))
      (node (ref "SW_Q") (pin "2") (pinfunction "2_2") (pintype "unspecified"))
    )
    (net (code "35") (name "Net-(D26-C)") (class "Default")
      (node (ref "CN1") (pin "6") (pinfunction "6_6") (pintype "unspecified"))
      (node (ref "D26") (pin "1") (pinfunction "C_1") (pintype "unspecified"))
    )
    (net (code "36") (name "Net-(D27-C)") (class "Default")
      (node (ref "CN1") (pin "4") (pinfunction "4_4") (pintype "unspecified"))
      (node (ref "D27") (pin "1") (pinfunction "C_1") (pintype "unspecified"))
    )
    (net (code "37") (name "Net-(D28-C)") (class "Default")
      (node (ref "CN1") (pin "2") (pinfunction "2_2") (pintype "unspecified"))
      (node (ref "D28") (pin "1") (pinfunction "C_1") (pintype "unspecified"))
    )
    (net (code "38") (name "Net-(D29-C)") (class "Default")
      (node (ref "CN2") (pin "8") (pinfunction "8_8") (pintype "unspecified"))
      (node (ref "D29") (pin "1") (pinfunction "C_1") (pintype "unspecified"))
    )
    (net (code "39") (name "Net-(D30-C)") (class "Default")
      (node (ref "CN2") (pin "6") (pinfunction "6_6") (pintype "unspecified"))
      (node (ref "D30") (pin "1") (pinfunction "C_1") (pintype "unspecified"))
    )
    (net (code "40") (name "Net-(D31-C)") (class "Default")
      (node (ref "CN2") (pin "4") (pinfunction "4_4") (pintype "unspecified"))
      (node (ref "D31") (pin "1") (pinfunction "C_1") (pintype "unspecified"))
    )
    (net (code "41") (name "Net-(D32-C)") (class "Default")
      (node (ref "CN2") (pin "2") (pinfunction "2_2") (pintype "unspecified"))
      (node (ref "D32") (pin "1") (pinfunction "C_1") (pintype "unspecified"))
    )
    (net (code "42") (name "Net-(P1-A0)") (class "Default")
      (node (ref "CN4") (pin "5") (pinfunction "5_5") (pintype "unspecified"))
      (node (ref "P1") (pin "20") (pinfunction "A0_20") (pintype "unspecified"))
    )
    (net (code "43") (name "Net-(P1-A1)") (class "Default")
      (node (ref "CN4") (pin "4") (pinfunction "4_4") (pintype "unspecified"))
      (node (ref "P1") (pin "19") (pinfunction "A1_19") (pintype "unspecified"))
    )
    (net (code "44") (name "Net-(P1-RST)") (class "Default")
      (node (ref "CN3") (pin "3") (pinfunction "3_3") (pintype "unspecified"))
      (node (ref "P1") (pin "15") (pinfunction "RST_15") (pintype "unspecified"))
      (node (ref "S1") (pin "1") (pinfunction "1_1") (pintype "unspecified"))
    )
    (net (code "45") (name "Net-(P1-RXI)") (class "Default")
      (node (ref "CN3") (pin "1") (pinfunction "1_1") (pintype "unspecified"))
      (node (ref "P1") (pin "11") (pinfunction "RXI_11") (pintype "unspecified"))
    )
    (net (code "46") (name "Net-(P1-TXO)") (class "Default")
      (node (ref "CN3") (pin "2") (pinfunction "2_2") (pintype "unspecified"))
      (node (ref "P1") (pin "12") (pinfunction "TXO_12") (pintype "unspecified"))
    )
    (net (code "47") (name "Row1") (class "Default")
      (node (ref "CN1") (pin "7") (pinfunction "7_7") (pintype "unspecified"))
      (node (ref "CN2") (pin "7") (pinfunction "7_7") (pintype "unspecified"))
      (node (ref "P1") (pin "24") (pinfunction "D10_24") (pintype "unspecified"))
      (node (ref "SW_E") (pin "1") (pinfunction "1_1") (pintype "unspecified"))
      (node (ref "SW_Q") (pin "1") (pinfunction "1_1") (pintype "unspecified"))
      (node (ref "SW_R") (pin "1") (pinfunction "1_1") (pintype "unspecified"))
      (node (ref "SW_T") (pin "1") (pinfunction "1_1") (pintype "unspecified"))
      (node (ref "SW_TAB") (pin "1") (pinfunction "1_1") (pintype "unspecified"))
      (node (ref "SW_W") (pin "1") (pinfunction "1_1") (pintype "unspecified"))
    )
    (net (code "48") (name "Row2") (class "Default")
      (node (ref "CN1") (pin "5") (pinfunction "5_5") (pintype "unspecified"))
      (node (ref "CN2") (pin "5") (pinfunction "5_5") (pintype "unspecified"))
      (node (ref "P1") (pin "23") (pinfunction "D16_23") (pintype "unspecified"))
      (node (ref "SW_A") (pin "1") (pinfunction "1_1") (pintype "unspecified"))
      (node (ref "SW_D") (pin "1") (pinfunction "1_1") (pintype "unspecified"))
      (node (ref "SW_ESC") (pin "1") (pinfunction "1_1") (pintype "unspecified"))
      (node (ref "SW_F") (pin "1") (pinfunction "1_1") (pintype "unspecified"))
      (node (ref "SW_G") (pin "1") (pinfunction "1_1") (pintype "unspecified"))
      (node (ref "SW_S") (pin "1") (pinfunction "1_1") (pintype "unspecified"))
    )
    (net (code "49") (name "Row3") (class "Default")
      (node (ref "CN1") (pin "3") (pinfunction "3_3") (pintype "unspecified"))
      (node (ref "CN2") (pin "3") (pinfunction "3_3") (pintype "unspecified"))
      (node (ref "P1") (pin "22") (pinfunction "D14_22") (pintype "unspecified"))
      (node (ref "SW_B") (pin "1") (pinfunction "1_1") (pintype "unspecified"))
      (node (ref "SW_C") (pin "1") (pinfunction "1_1") (pintype "unspecified"))
      (node (ref "SW_SHIFT") (pin "1") (pinfunction "1_1") (pintype "unspecified"))
      (node (ref "SW_V") (pin "1") (pinfunction "1_1") (pintype "unspecified"))
      (node (ref "SW_X") (pin "1") (pinfunction "1_1") (pintype "unspecified"))
      (node (ref "SW_Z") (pin "1") (pinfunction "1_1") (pintype "unspecified"))
    )
    (net (code "50") (name "Row4") (class "Default")
      (node (ref "CN1") (pin "1") (pinfunction "1_1") (pintype "unspecified"))
      (node (ref "CN2") (pin "1") (pinfunction "1_1") (pintype "unspecified"))
      (node (ref "P1") (pin "21") (pinfunction "D15_21") (pintype "unspecified"))
      (node (ref "SW_ALT") (pin "1") (pinfunction "1_1") (pintype "unspecified"))
      (node (ref "SW_CTRL") (pin "1") (pinfunction "1_1") (pintype "unspecified"))
      (node (ref "SW_FN") (pin "1") (pinfunction "1_1") (pintype "unspecified"))
      (node (ref "SW_LOWER") (pin "1") (pinfunction "1_1") (pintype "unspecified"))
      (node (ref "SW_SPACE") (pin "1") (pinfunction "1_1") (pintype "unspecified"))
      (node (ref "SW_SUPER") (pin "1") (pinfunction "1_1") (pintype "unspecified"))
    )
    (net (code "51") (name "SCL") (class "Default")
      (node (ref "CN4") (pin "2") (pinfunction "2_2") (pintype "unspecified"))
      (node (ref "P1") (pin "7") (pinfunction "D3_7") (pintype "unspecified"))
      (node (ref "R7") (pin "2") (pinfunction "2_2") (pintype "unspecified"))
      (node (ref "U1") (pin "RING1") (pinfunction "RING1_RING1") (pintype "unspecified"))
      (node (ref "U2") (pin "RING1") (pinfunction "RING1_RING1") (pintype "unspecified"))
    )
    (net (code "52") (name "SDA") (class "Default")
      (node (ref "CN4") (pin "3") (pinfunction "3_3") (pintype "unspecified"))
      (node (ref "P1") (pin "8") (pinfunction "D2_8") (pintype "unspecified"))
      (node (ref "R8") (pin "2") (pinfunction "2_2") (pintype "unspecified"))
      (node (ref "U1") (pin "RING2") (pinfunction "RING2_RING2") (pintype "unspecified"))
      (node (ref "U2") (pin "RING2") (pinfunction "RING2_RING2") (pintype "unspecified"))
    )
    (net (code "53") (name "VCC") (class "Default")
      (node (ref "CN3") (pin "5") (pinfunction "5_5") (pintype "unspecified"))
      (node (ref "P1") (pin "16") (pinfunction "VCC_16") (pintype "unspecified"))
      (node (ref "R1") (pin "2") (pinfunction "2_2") (pintype "unspecified"))
      (node (ref "R10") (pin "2") (pinfunction "2_2") (pintype "unspecified"))
      (node (ref "R2") (pin "2") (pinfunction "2_2") (pintype "unspecified"))
      (node (ref "R3") (pin "2") (pinfunction "2_2") (pintype "unspecified"))
      (node (ref "R4") (pin "2") (pinfunction "2_2") (pintype "unspecified"))
      (node (ref "R5") (pin "2") (pinfunction "2_2") (pintype "unspecified"))
      (node (ref "R6") (pin "2") (pinfunction "2_2") (pintype "unspecified"))
      (node (ref "R7") (pin "1") (pinfunction "1_1") (pintype "unspecified"))
      (node (ref "R8") (pin "1") (pinfunction "1_1") (pintype "unspecified"))
      (node (ref "R9") (pin "2") (pinfunction "2_2") (pintype "unspecified"))
      (node (ref "U1") (pin "TIP") (pinfunction "TIP_TIP") (pintype "unspecified"))
      (node (ref "U2") (pin "TIP") (pinfunction "TIP_TIP") (pintype "unspecified"))
    )
    (net (code "54") (name "unconnected-(P1-RAW-Pad13)") (class "Default")
      (node (ref "P1") (pin "13") (pinfunction "RAW_13") (pintype "unspecified+no_connect"))
    )
  )
)
